# 6_Power.net
KiCad netlist of a schematic drawn in Altium Designer
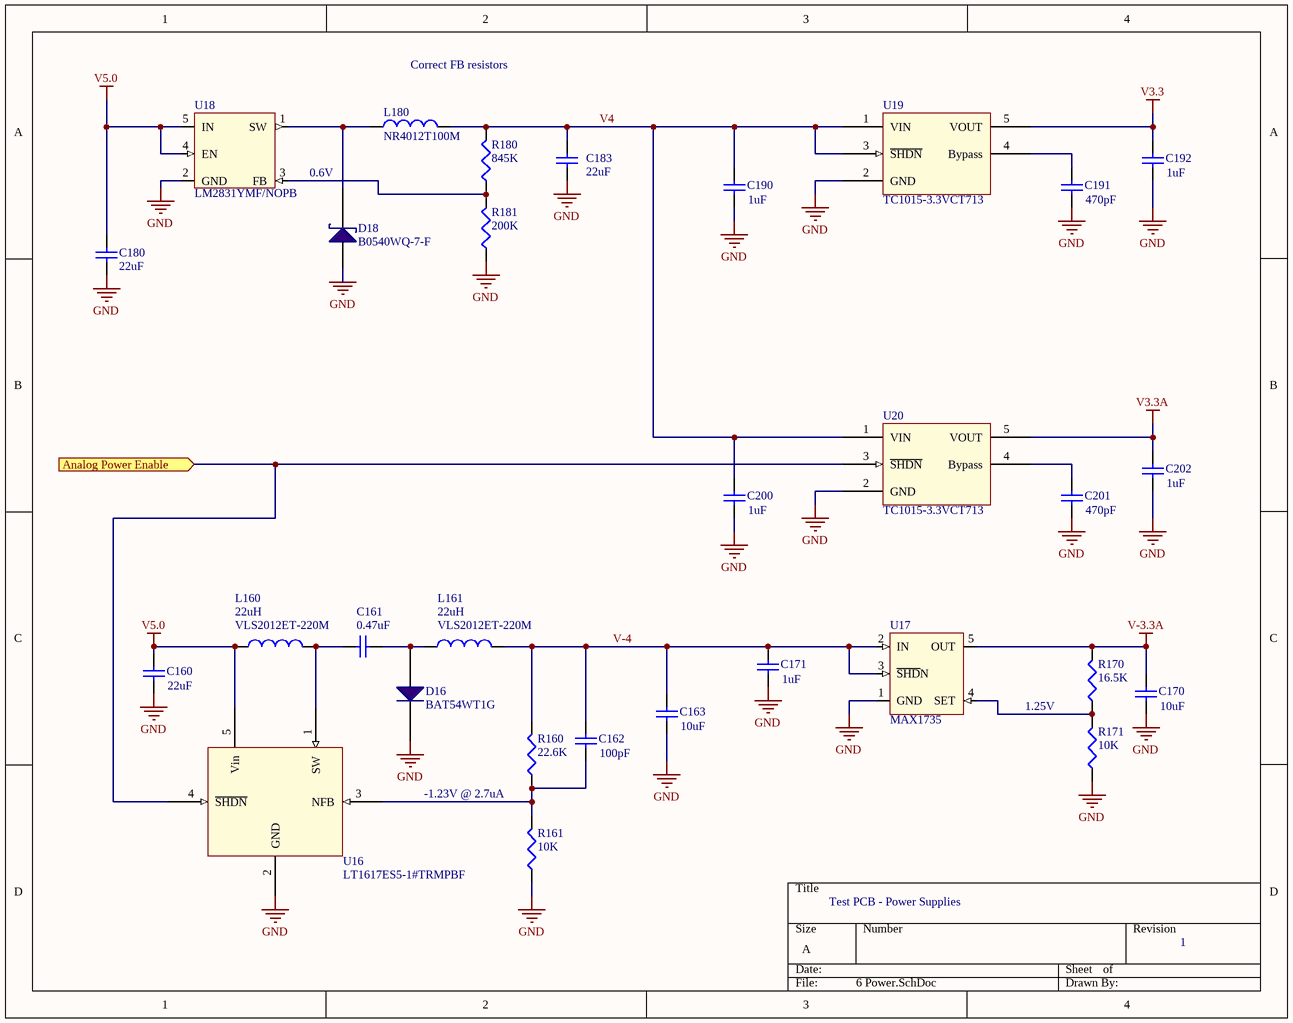
[diagram p0: 6 Power.SchDoc]

(export (version "E")
  (design (tool "Eeschema 10.0.6"))
  (components
    (comp (ref "C160")
      (value "22uF")
      (footprint "C0805")
      (description "Capacitor, SM")
      (fields (field (name "PUBLISHER") "Altium Limited"))
      (libsource (lib "Graylark") (part "Cap SM"))
    )
    (comp (ref "C161")
      (value "0.47uF")
      (footprint "C0603")
      (description "Capacitor, SM")
      (fields (field (name "PUBLISHER") "Altium Limited"))
      (libsource (lib "Graylark") (part "Cap SM"))
    )
    (comp (ref "C162")
      (value "100pF")
      (footprint "C0603")
      (description "Capacitor, SM")
      (fields (field (name "PUBLISHER") "Altium Limited"))
      (libsource (lib "Graylark") (part "Cap SM"))
    )
    (comp (ref "C163")
      (value "10uF")
      (footprint "C0805")
      (description "Capacitor, SM")
      (fields (field (name "PUBLISHER") "Altium Limited"))
      (libsource (lib "Graylark") (part "Cap SM"))
    )
    (comp (ref "C170")
      (value "10uF")
      (footprint "C0805")
      (description "Capacitor, SM")
      (fields (field (name "PUBLISHER") "Altium Limited"))
      (libsource (lib "Graylark") (part "Cap SM"))
    )
    (comp (ref "C171")
      (value "1uF")
      (footprint "C0603")
      (description "Capacitor, SM")
      (fields (field (name "PUBLISHER") "Altium Limited"))
      (libsource (lib "Graylark") (part "Cap SM"))
    )
    (comp (ref "C180")
      (value "22uF")
      (footprint "C0805")
      (description "Capacitor, SM")
      (fields (field (name "PUBLISHER") "Altium Limited"))
      (libsource (lib "Graylark") (part "Cap SM"))
    )
    (comp (ref "C183")
      (value "22uF")
      (footprint "C0805")
      (description "Capacitor, SM")
      (fields (field (name "PUBLISHER") "Altium Limited"))
      (libsource (lib "Graylark") (part "Cap SM"))
    )
    (comp (ref "C190")
      (value "1uF")
      (footprint "C0603")
      (description "Capacitor, SM")
      (fields (field (name "PUBLISHER") "Altium Limited"))
      (libsource (lib "Graylark") (part "Cap SM"))
    )
    (comp (ref "C191")
      (value "470pF")
      (footprint "C0603")
      (description "Capacitor, SM")
      (fields (field (name "PUBLISHER") "Altium Limited"))
      (libsource (lib "Graylark") (part "Cap SM"))
    )
    (comp (ref "C192")
      (value "1uF")
      (footprint "C0603")
      (description "Capacitor, SM")
      (fields (field (name "PUBLISHER") "Altium Limited"))
      (libsource (lib "Graylark") (part "Cap SM"))
    )
    (comp (ref "C200")
      (value "1uF")
      (footprint "C0603")
      (description "Capacitor, SM")
      (fields (field (name "PUBLISHER") "Altium Limited"))
      (libsource (lib "Graylark") (part "Cap SM"))
    )
    (comp (ref "C201")
      (value "470pF")
      (footprint "C0603")
      (description "Capacitor, SM")
      (fields (field (name "PUBLISHER") "Altium Limited"))
      (libsource (lib "Graylark") (part "Cap SM"))
    )
    (comp (ref "C202")
      (value "1uF")
      (footprint "C0603")
      (description "Capacitor, SM")
      (fields (field (name "PUBLISHER") "Altium Limited"))
      (libsource (lib "Graylark") (part "Cap SM"))
    )
    (comp (ref "D16") (value "BAT54WT1G") (footprint "SC70-3") (libsource (lib "Graylark") (part "BAT54W")))
    (comp (ref "D18")
      (value "B0540WQ-7-F")
      (footprint "SOD123W")
      (description "Schottky diode")
      (libsource (lib "Graylark") (part "BAT46W"))
    )
    (comp (ref "L160")
      (value "VLS2012ET-220M")
      (footprint "L_2012")
      (fields (field (name "ALTIUM_VALUE") "22uH"))
      (libsource (lib "Graylark") (part "Inductor"))
    )
    (comp (ref "L161")
      (value "VLS2012ET-220M")
      (footprint "L_2012")
      (fields (field (name "ALTIUM_VALUE") "22uH"))
      (libsource (lib "Graylark") (part "Inductor"))
    )
    (comp (ref "L180")
      (value "NR4012T100M")
      (footprint "L_4018")
      (libsource (lib "Graylark") (part "Inductor"))
    )
    (comp (ref "R160")
      (value "22.6K")
      (footprint "R0603")
      (description "Resistor")
      (fields (field (name "PUBLISHER") "Altium Limited"))
      (libsource (lib "Graylark") (part "Res SM"))
    )
    (comp (ref "R161")
      (value "10K")
      (footprint "R0603")
      (description "Resistor")
      (fields (field (name "PUBLISHER") "Altium Limited"))
      (libsource (lib "Graylark") (part "Res SM"))
    )
    (comp (ref "R170")
      (value "16.5K")
      (footprint "R0603")
      (description "Resistor")
      (fields (field (name "PUBLISHER") "Altium Limited"))
      (libsource (lib "Graylark") (part "Res SM"))
    )
    (comp (ref "R171")
      (value "10K")
      (footprint "R0603")
      (description "Resistor")
      (fields (field (name "PUBLISHER") "Altium Limited"))
      (libsource (lib "Graylark") (part "Res SM"))
    )
    (comp (ref "R180")
      (value "845K")
      (footprint "R0603")
      (description "Resistor")
      (fields (field (name "PUBLISHER") "Altium Limited"))
      (libsource (lib "Graylark") (part "Res SM"))
    )
    (comp (ref "R181")
      (value "200K")
      (footprint "R0603")
      (description "Resistor")
      (fields (field (name "PUBLISHER") "Altium Limited"))
      (libsource (lib "Graylark") (part "Res SM"))
    )
    (comp (ref "U16")
      (value "LT1617ES5-1#TRMPBF")
      (footprint "SOT23-5")
      (libsource (lib "Graylark") (part "LT1617-1"))
    )
    (comp (ref "U17") (value "MAX1735") (footprint "SOT23-5") (libsource (lib "Graylark") (part "MAX1735")))
    (comp (ref "U18")
      (value "LM2831YMF/NOPB")
      (footprint "SOT23-5")
      (libsource (lib "Graylark") (part "LM2831"))
    )
    (comp (ref "U19")
      (value "TC1015-3.3VCT713")
      (footprint "SOT23-5")
      (libsource (lib "Graylark") (part "TC1014"))
    )
    (comp (ref "U20")
      (value "TC1015-3.3VCT713")
      (footprint "SOT23-5")
      (libsource (lib "Graylark") (part "TC1014"))
    )
  )
  (nets
    (net (code "1") (name "/Analog Power Enable") (class "Default")
      (node (ref "U16") (pin "4") (pinfunction "~{SHDN}_4") (pintype "input"))
      (node (ref "U20") (pin "3") (pinfunction "~{SHDN}_3") (pintype "input"))
    )
    (net (code "2") (name "/V-4") (class "Default")
      (node (ref "C162") (pin "2") (pinfunction "2_2") (pintype "passive"))
      (node (ref "C163") (pin "2") (pinfunction "2_2") (pintype "passive"))
      (node (ref "C171") (pin "2") (pinfunction "2_2") (pintype "passive"))
      (node (ref "L161") (pin "2") (pinfunction "2_2") (pintype "passive"))
      (node (ref "R160") (pin "2") (pinfunction "2_2") (pintype "passive"))
      (node (ref "U17") (pin "2") (pinfunction "IN_2") (pintype "input"))
      (node (ref "U17") (pin "3") (pinfunction "~{SHD}N_3") (pintype "input"))
    )
    (net (code "3") (name "/V4") (class "Default")
      (node (ref "C183") (pin "2") (pinfunction "2_2") (pintype "passive"))
      (node (ref "C190") (pin "2") (pinfunction "2_2") (pintype "passive"))
      (node (ref "C200") (pin "2") (pinfunction "2_2") (pintype "passive"))
      (node (ref "L180") (pin "2") (pinfunction "2_2") (pintype "passive"))
      (node (ref "R180") (pin "2") (pinfunction "2_2") (pintype "passive"))
      (node (ref "U19") (pin "1") (pinfunction "VIN_1") (pintype "power_in"))
      (node (ref "U19") (pin "3") (pinfunction "~{SHDN}_3") (pintype "input"))
      (node (ref "U20") (pin "1") (pinfunction "VIN_1") (pintype "power_in"))
    )
    (net (code "4") (name "GND") (class "Default")
      (node (ref "C160") (pin "1") (pinfunction "1_1") (pintype "passive"))
      (node (ref "C163") (pin "1") (pinfunction "1_1") (pintype "passive"))
      (node (ref "C170") (pin "1") (pinfunction "1_1") (pintype "passive"))
      (node (ref "C171") (pin "1") (pinfunction "1_1") (pintype "passive"))
      (node (ref "C180") (pin "1") (pinfunction "1_1") (pintype "passive"))
      (node (ref "C183") (pin "1") (pinfunction "1_1") (pintype "passive"))
      (node (ref "C190") (pin "1") (pinfunction "1_1") (pintype "passive"))
      (node (ref "C191") (pin "1") (pinfunction "1_1") (pintype "passive"))
      (node (ref "C192") (pin "1") (pinfunction "1_1") (pintype "passive"))
      (node (ref "C200") (pin "1") (pinfunction "1_1") (pintype "passive"))
      (node (ref "C201") (pin "1") (pinfunction "1_1") (pintype "passive"))
      (node (ref "C202") (pin "1") (pinfunction "1_1") (pintype "passive"))
      (node (ref "D16") (pin "3") (pinfunction "3_3") (pintype "passive"))
      (node (ref "D18") (pin "1") (pinfunction "1_1") (pintype "passive"))
      (node (ref "R161") (pin "1") (pinfunction "1_1") (pintype "passive"))
      (node (ref "R171") (pin "1") (pinfunction "1_1") (pintype "passive"))
      (node (ref "R181") (pin "1") (pinfunction "1_1") (pintype "passive"))
      (node (ref "U16") (pin "2") (pinfunction "GND_2") (pintype "power_in"))
      (node (ref "U17") (pin "1") (pinfunction "GND_1") (pintype "power_in"))
      (node (ref "U18") (pin "2") (pinfunction "GND_2") (pintype "power_in"))
      (node (ref "U19") (pin "2") (pinfunction "GND_2") (pintype "power_in"))
      (node (ref "U20") (pin "2") (pinfunction "GND_2") (pintype "power_in"))
    )
    (net (code "5") (name "Net-(C161-Pad2)") (class "Default")
      (node (ref "C161") (pin "2") (pinfunction "2_2") (pintype "passive"))
      (node (ref "D16") (pin "1") (pinfunction "1_1") (pintype "passive"))
      (node (ref "L161") (pin "1") (pinfunction "1_1") (pintype "passive"))
    )
    (net (code "6") (name "Net-(U16-NFB)") (class "Default")
      (node (ref "C162") (pin "1") (pinfunction "1_1") (pintype "passive"))
      (node (ref "R160") (pin "1") (pinfunction "1_1") (pintype "passive"))
      (node (ref "R161") (pin "2") (pinfunction "2_2") (pintype "passive"))
      (node (ref "U16") (pin "3") (pinfunction "NFB_3") (pintype "input"))
    )
    (net (code "7") (name "Net-(U16-SW)") (class "Default")
      (node (ref "C161") (pin "1") (pinfunction "1_1") (pintype "passive"))
      (node (ref "L160") (pin "2") (pinfunction "2_2") (pintype "passive"))
      (node (ref "U16") (pin "1") (pinfunction "SW_1") (pintype "input"))
    )
    (net (code "8") (name "Net-(U17-SET)") (class "Default")
      (node (ref "R170") (pin "1") (pinfunction "1_1") (pintype "passive"))
      (node (ref "R171") (pin "2") (pinfunction "2_2") (pintype "passive"))
      (node (ref "U17") (pin "4") (pinfunction "SET_4") (pintype "input"))
    )
    (net (code "9") (name "Net-(U18-FB)") (class "Default")
      (node (ref "R180") (pin "1") (pinfunction "1_1") (pintype "passive"))
      (node (ref "R181") (pin "2") (pinfunction "2_2") (pintype "passive"))
      (node (ref "U18") (pin "3") (pinfunction "FB_3") (pintype "input"))
    )
    (net (code "10") (name "Net-(U18-SW)") (class "Default")
      (node (ref "D18") (pin "2") (pinfunction "2_2") (pintype "passive"))
      (node (ref "L180") (pin "1") (pinfunction "1_1") (pintype "passive"))
      (node (ref "U18") (pin "1") (pinfunction "SW_1") (pintype "output"))
    )
    (net (code "11") (name "Net-(U19-Bypass)") (class "Default")
      (node (ref "C191") (pin "2") (pinfunction "2_2") (pintype "passive"))
      (node (ref "U19") (pin "4") (pinfunction "Bypass_4") (pintype "passive"))
    )
    (net (code "12") (name "Net-(U20-Bypass)") (class "Default")
      (node (ref "C201") (pin "2") (pinfunction "2_2") (pintype "passive"))
      (node (ref "U20") (pin "4") (pinfunction "Bypass_4") (pintype "passive"))
    )
    (net (code "13") (name "V-3.3A") (class "Default")
      (node (ref "C170") (pin "2") (pinfunction "2_2") (pintype "passive"))
      (node (ref "R170") (pin "2") (pinfunction "2_2") (pintype "passive"))
      (node (ref "U17") (pin "5") (pinfunction "OUT_5") (pintype "power_in"))
    )
    (net (code "14") (name "V3.3") (class "Default")
      (node (ref "C192") (pin "2") (pinfunction "2_2") (pintype "passive"))
      (node (ref "U19") (pin "5") (pinfunction "VOUT_5") (pintype "power_in"))
    )
    (net (code "15") (name "V3.3A") (class "Default")
      (node (ref "C202") (pin "2") (pinfunction "2_2") (pintype "passive"))
      (node (ref "U20") (pin "5") (pinfunction "VOUT_5") (pintype "power_in"))
    )
    (net (code "16") (name "V5.0") (class "Default")
      (node (ref "C160") (pin "2") (pinfunction "2_2") (pintype "passive"))
      (node (ref "C180") (pin "2") (pinfunction "2_2") (pintype "passive"))
      (node (ref "L160") (pin "1") (pinfunction "1_1") (pintype "passive"))
      (node (ref "U16") (pin "5") (pinfunction "Vin_5") (pintype "power_in"))
      (node (ref "U18") (pin "4") (pinfunction "EN_4") (pintype "input"))
      (node (ref "U18") (pin "5") (pinfunction "IN_5") (pintype "power_in"))
    )
  )
)
